# HW1_74.net
KiCad netlist of a schematic drawn in EasyEDA
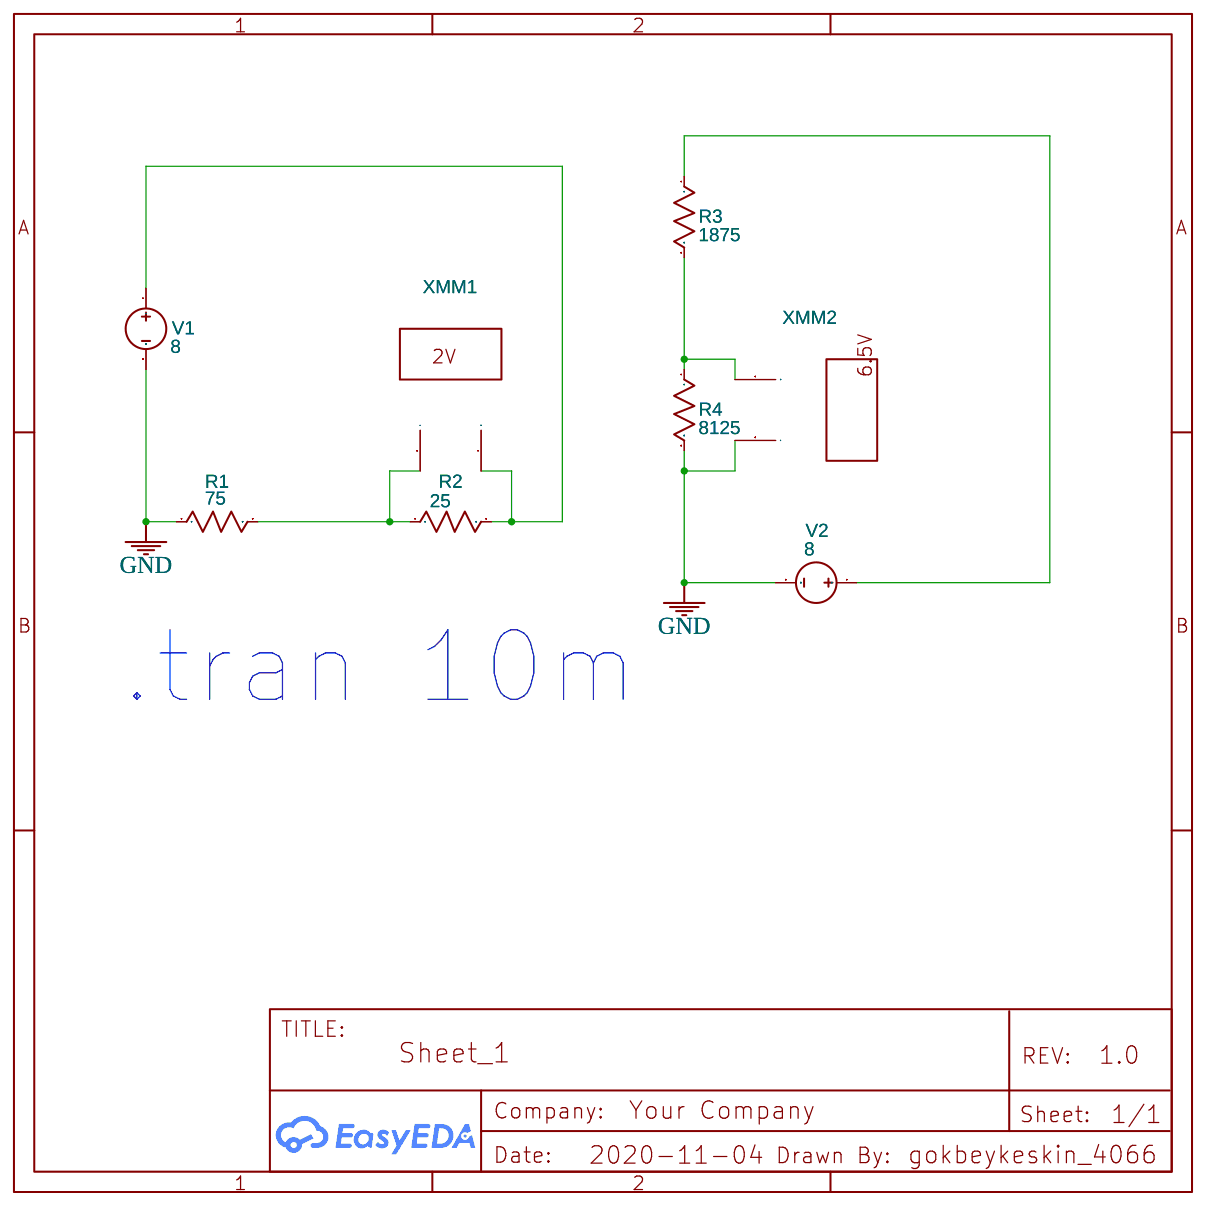
[diagram p0: schematic sheet]

(export (version "E")
  (design (tool "Eeschema 10.0.6"))
  (components
    (comp (ref "R1") (value "75") (libsource (lib "") (part "Resistor_US_1")))
    (comp (ref "R2") (value "25") (libsource (lib "") (part "Resistor_US_1")))
    (comp (ref "R3") (value "1875") (libsource (lib "") (part "Resistor_US")))
    (comp (ref "R4") (value "8125") (libsource (lib "") (part "Resistor_US")))
    (comp (ref "V1") (value "8") (libsource (lib "") (part "VDC_1")))
    (comp (ref "V2") (value "8") (libsource (lib "") (part "VDC")))
    (comp (ref "XMM1") (value "Multimeter") (libsource (lib "") (part "MULTIMETER_1")))
    (comp (ref "XMM2") (value "Multimeter") (libsource (lib "") (part "MULTIMETER")))
  )
  (nets
    (net (code "1") (name "GND") (class "Default")
      (node (ref "R1") (pin "1") (pinfunction "1_1") (pintype "unspecified"))
      (node (ref "R4") (pin "2") (pinfunction "2_2") (pintype "unspecified"))
      (node (ref "V1") (pin "2") (pinfunction "2_2") (pintype "unspecified"))
      (node (ref "V2") (pin "2") (pinfunction "2_2") (pintype "unspecified"))
      (node (ref "XMM2") (pin "2") (pinfunction "I_2") (pintype "unspecified"))
    )
    (net (code "2") (name "Net-(R3-Pad1)") (class "Default")
      (node (ref "R3") (pin "1") (pinfunction "1_1") (pintype "unspecified"))
      (node (ref "V2") (pin "1") (pinfunction "1_1") (pintype "unspecified"))
    )
    (net (code "3") (name "Net-(XMM1-+)") (class "Default")
      (node (ref "R2") (pin "2") (pinfunction "2_2") (pintype "unspecified"))
      (node (ref "V1") (pin "1") (pinfunction "1_1") (pintype "unspecified"))
      (node (ref "XMM1") (pin "1") (pinfunction "+_1") (pintype "unspecified"))
    )
    (net (code "4") (name "Net-(XMM1-I)") (class "Default")
      (node (ref "R1") (pin "2") (pinfunction "2_2") (pintype "unspecified"))
      (node (ref "R2") (pin "1") (pinfunction "1_1") (pintype "unspecified"))
      (node (ref "XMM1") (pin "2") (pinfunction "I_2") (pintype "unspecified"))
    )
    (net (code "5") (name "Net-(XMM2-+)") (class "Default")
      (node (ref "R3") (pin "2") (pinfunction "2_2") (pintype "unspecified"))
      (node (ref "R4") (pin "1") (pinfunction "1_1") (pintype "unspecified"))
      (node (ref "XMM2") (pin "1") (pinfunction "+_1") (pintype "unspecified"))
    )
  )
)
